# 2_MICROCONTROLADOR.net
KiCad netlist of a schematic drawn in Altium Designer
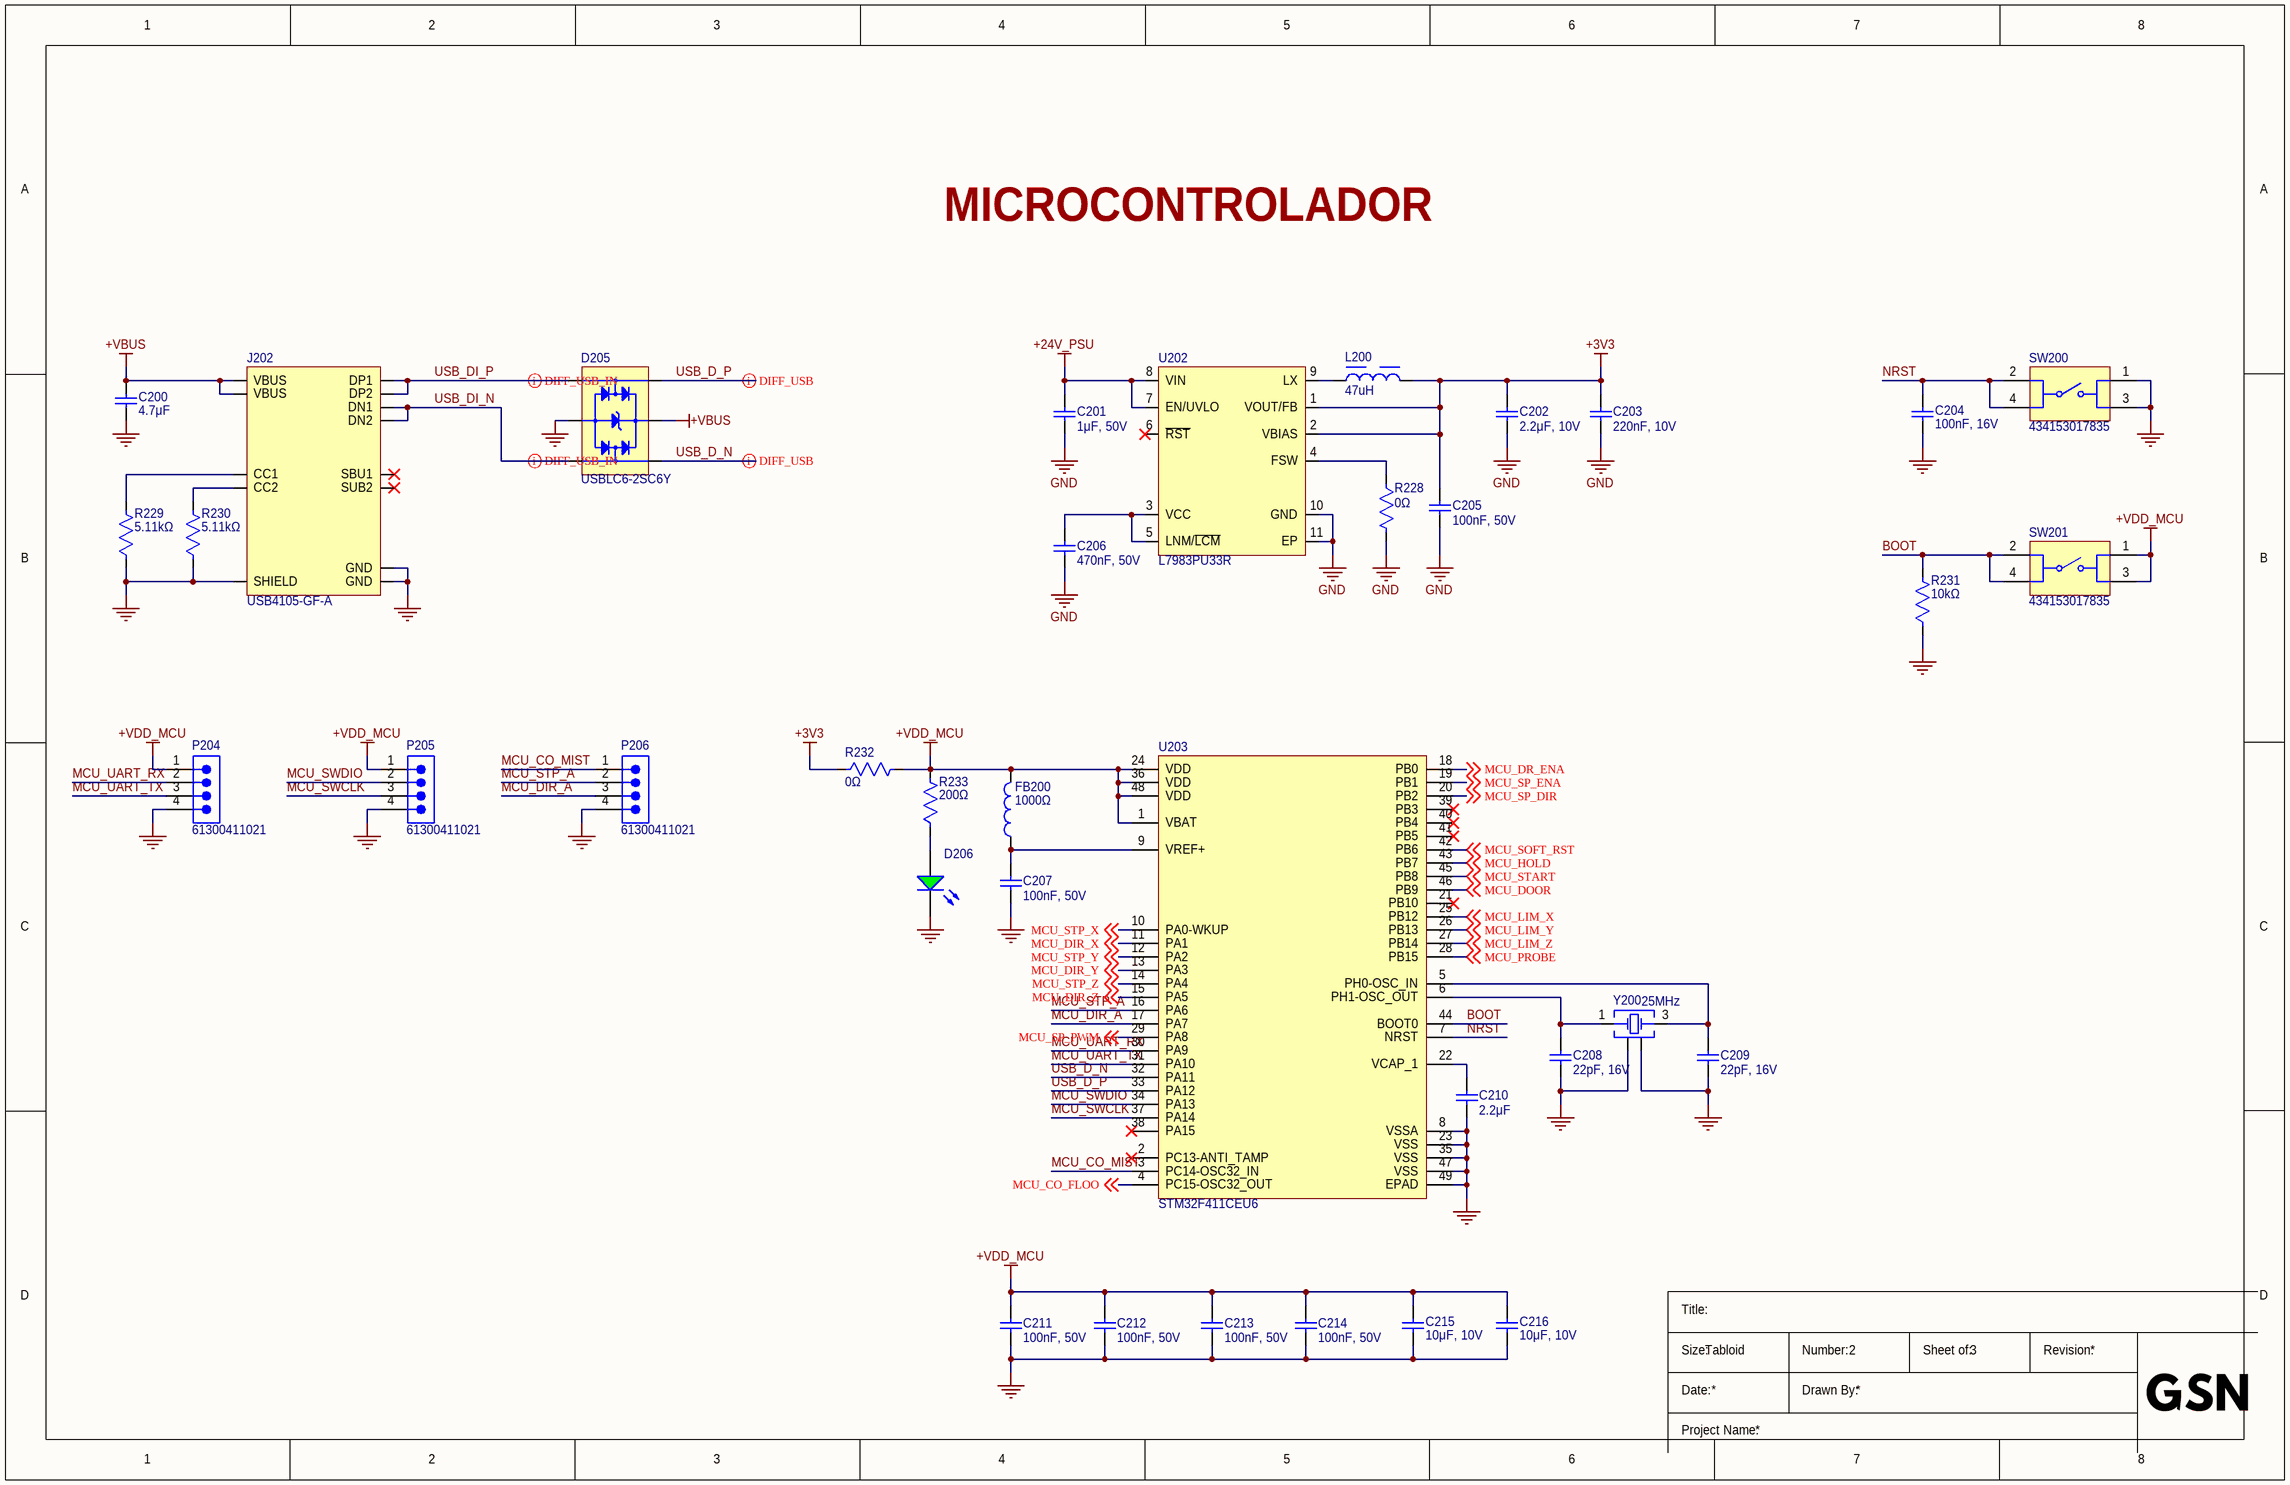
[diagram p0: 2_MICROCONTROLADOR.SchDoc]

(export (version "E")
  (design (tool "Eeschema 10.0.6"))
  (components
    (comp (ref "C200")
      (value "4.7μF")
      (footprint "WCAP-CSGP_0805_L2W1.25H1.25")
      (description "WCAP-CSGP Multilayer Ceramic Chip Capacitor, General Purpose, size 0805, 4.7μF, 16V")
      (fields
        (field (name "MANUFACTURER PART NUMBER") "885012207053")
        (field (name "MANUFACTURER") "Wurth Elektronik")
      )
      (libsource (lib "WE - Passive Components") (part "Capacitor_Non-Polarized"))
    )
    (comp (ref "C201")
      (value "1μF, 50V")
      (footprint "WCAP-CSGP_0805_L2W1.25H1.25")
      (description "WCAP-CSGP Multilayer Ceramic Chip Capacitor, General Purpose, size 0805, 1μF, 50V")
      (fields
        (field (name "MANUFACTURER PART NUMBER") "885012207103R")
        (field (name "MANUFACTURER") "Wurth Elektronik")
      )
      (libsource (lib "WE - Passive Components") (part "Capacitor_Non-Polarized"))
    )
    (comp (ref "C202")
      (value "2.2μF, 10V")
      (footprint "WCAP-CSGP_0603_L1.6W0.8H0.8_Wave")
      (description "WCAP-CSGP Multilayer Ceramic Chip Capacitor, General Purpose, size 0603, 2.2μF, 10V")
      (fields
        (field (name "MANUFACTURER PART NUMBER") "885012206027")
        (field (name "MANUFACTURER") "Wurth Elektronik")
      )
      (libsource (lib "WE - Passive Components") (part "Capacitor_Non-Polarized"))
    )
    (comp (ref "C203")
      (value "220nF, 10V")
      (footprint "WCAP-CSGP_0603_L1.6W0.8H0.8_Wave")
      (description "WCAP-CSGP Multilayer Ceramic Chip Capacitor, General Purpose, size 0603, 220nF, 10V")
      (fields
        (field (name "MANUFACTURER PART NUMBER") "885012206022")
        (field (name "MANUFACTURER") "Wurth Elektronik")
      )
      (libsource (lib "WE - Passive Components") (part "Capacitor_Non-Polarized"))
    )
    (comp (ref "C204")
      (value "100nF, 16V")
      (footprint "WCAP-CSGP_0603_L1.6W0.8H0.8_Wave")
      (description "WCAP-CSGP Multilayer Ceramic Chip Capacitor, General Purpose, size 0603, 100nF, 16V")
      (fields
        (field (name "MANUFACTURER PART NUMBER") "885012206046")
        (field (name "MANUFACTURER") "Wurth Elektronik")
      )
      (libsource (lib "WE - Passive Components") (part "Capacitor_Non-Polarized"))
    )
    (comp (ref "C205")
      (value "100nF, 50V")
      (footprint "WCAP-CSGP_0603_L1.6W0.8H0.8_Wave")
      (description "WCAP-CSGP Multilayer Ceramic Chip Capacitor, General Purpose, size 0603, 100nF, 50V")
      (fields
        (field (name "MANUFACTURER PART NUMBER") "885012206095")
        (field (name "MANUFACTURER") "Wurth Elektronik")
      )
      (libsource (lib "WE - Passive Components") (part "Capacitor_Non-Polarized"))
    )
    (comp (ref "C206")
      (value "470nF, 50V")
      (footprint "WCAP-CSGP_0805_L2W1.25H1.25")
      (description "WCAP-CSGP Multilayer Ceramic Chip Capacitor, General Purpose, size 0805, 470nF, 50V")
      (fields
        (field (name "MANUFACTURER PART NUMBER") "885012207102")
        (field (name "MANUFACTURER") "Wurth Elektronik")
      )
      (libsource (lib "WE - Passive Components") (part "Capacitor_Non-Polarized"))
    )
    (comp (ref "C207")
      (value "100nF, 50V")
      (footprint "WCAP-CSGP_0603_L1.6W0.8H0.8_Wave")
      (description "WCAP-CSGP Multilayer Ceramic Chip Capacitor, General Purpose, size 0603, 100nF, 50V")
      (fields
        (field (name "MANUFACTURER PART NUMBER") "885012206095")
        (field (name "MANUFACTURER") "Wurth Elektronik")
      )
      (libsource (lib "WE - Passive Components") (part "Capacitor_Non-Polarized"))
    )
    (comp (ref "C208")
      (value "22pF, 16V")
      (footprint "WCAP-CSGP_0603_L1.6W0.8H0.8_Wave")
      (description "WCAP-CSGP Multilayer Ceramic Chip Capacitor, General Purpose, size 0603, 22pF, 16V")
      (fields
        (field (name "MANUFACTURER PART NUMBER") "885012006019")
        (field (name "MANUFACTURER") "Wurth Elektronik")
      )
      (libsource (lib "WE - Passive Components") (part "Capacitor_Non-Polarized"))
    )
    (comp (ref "C209")
      (value "22pF, 16V")
      (footprint "WCAP-CSGP_0603_L1.6W0.8H0.8_Wave")
      (description "WCAP-CSGP Multilayer Ceramic Chip Capacitor, General Purpose, size 0603, 22pF, 16V")
      (fields
        (field (name "MANUFACTURER PART NUMBER") "885012006019")
        (field (name "MANUFACTURER") "Wurth Elektronik")
      )
      (libsource (lib "WE - Passive Components") (part "Capacitor_Non-Polarized"))
    )
    (comp (ref "C210")
      (value "2.2μF")
      (footprint "WCAP-CSGP_0603_L1.6W0.8H0.8_Wave")
      (description "WCAP-CSGP Multilayer Ceramic Chip Capacitor, General Purpose, size 0603, 2.2μF, 6.3V")
      (fields
        (field (name "MANUFACTURER PART NUMBER") "885012106004")
        (field (name "MANUFACTURER") "Wurth Elektronik")
      )
      (libsource (lib "WE - Passive Components") (part "Capacitor_Non-Polarized"))
    )
    (comp (ref "C211")
      (value "100nF, 50V")
      (footprint "WCAP-CSGP_0603_L1.6W0.8H0.8_Wave")
      (description "WCAP-CSGP Multilayer Ceramic Chip Capacitor, General Purpose, size 0603, 100nF, 50V")
      (fields
        (field (name "MANUFACTURER PART NUMBER") "885012206095")
        (field (name "MANUFACTURER") "Wurth Elektronik")
      )
      (libsource (lib "WE - Passive Components") (part "Capacitor_Non-Polarized"))
    )
    (comp (ref "C212")
      (value "100nF, 50V")
      (footprint "WCAP-CSGP_0603_L1.6W0.8H0.8_Wave")
      (description "WCAP-CSGP Multilayer Ceramic Chip Capacitor, General Purpose, size 0603, 100nF, 50V")
      (fields
        (field (name "MANUFACTURER PART NUMBER") "885012206095")
        (field (name "MANUFACTURER") "Wurth Elektronik")
      )
      (libsource (lib "WE - Passive Components") (part "Capacitor_Non-Polarized"))
    )
    (comp (ref "C213")
      (value "100nF, 50V")
      (footprint "WCAP-CSGP_0603_L1.6W0.8H0.8_Wave")
      (description "WCAP-CSGP Multilayer Ceramic Chip Capacitor, General Purpose, size 0603, 100nF, 50V")
      (fields
        (field (name "MANUFACTURER PART NUMBER") "885012206095")
        (field (name "MANUFACTURER") "Wurth Elektronik")
      )
      (libsource (lib "WE - Passive Components") (part "Capacitor_Non-Polarized"))
    )
    (comp (ref "C214")
      (value "100nF, 50V")
      (footprint "WCAP-CSGP_0603_L1.6W0.8H0.8_Wave")
      (description "WCAP-CSGP Multilayer Ceramic Chip Capacitor, General Purpose, size 0603, 100nF, 50V")
      (fields
        (field (name "MANUFACTURER PART NUMBER") "885012206095")
        (field (name "MANUFACTURER") "Wurth Elektronik")
      )
      (libsource (lib "WE - Passive Components") (part "Capacitor_Non-Polarized"))
    )
    (comp (ref "C215")
      (value "10μF, 10V")
      (footprint "WCAP-CSGP_0805_L2W1.25H1.25")
      (description "WCAP-CSGP Multilayer Ceramic Chip Capacitor, General Purpose, size 0805, 10μF, 10V")
      (fields
        (field (name "MANUFACTURER PART NUMBER") "885012207026")
        (field (name "MANUFACTURER") "Wurth Elektronik")
      )
      (libsource (lib "WE - Passive Components") (part "Capacitor_Non-Polarized"))
    )
    (comp (ref "C216")
      (value "10μF, 10V")
      (footprint "WCAP-CSGP_0805_L2W1.25H1.25")
      (description "WCAP-CSGP Multilayer Ceramic Chip Capacitor, General Purpose, size 0805, 10μF, 10V")
      (fields
        (field (name "MANUFACTURER PART NUMBER") "885012207026")
        (field (name "MANUFACTURER") "Wurth Elektronik")
      )
      (libsource (lib "WE - Passive Components") (part "Capacitor_Non-Polarized"))
    )
    (comp (ref "D205")
      (value "USBLC6-2SC6Y")
      (footprint "SOT-23-6")
      (description "TVS DIODE 5.25VWM 17VC SOT23-6")
      (fields (field (name "MANUFACTURER") "STMicroelectronics"))
      (libsource (lib "TVS-Diodes") (part "USBLC6-2SC6Y"))
    )
    (comp (ref "D206")
      (value "Bright Green, 2V, 140deg")
      (footprint "WL-SMCW_0603_150060xx75000")
      (description "WL-SMCW Mono-color Chip LED Waterclear, SMT, size 0603, Bright Green, 2V, 140°")
      (fields
        (field (name "MANUFACTURER PART NUMBER") "150060VS75000")
        (field (name "MANUFACTURER") "Wurth Elektronik")
      )
      (libsource (lib "WE - Optoelectronic Components") (part "LED_Green_2A-1K"))
    )
    (comp (ref "FB200")
      (value "1000Ω")
      (footprint "WE-CBF_0603_L1.6W0.8H0.8_HS_WB")
      (description "WE-CBF SMT EMI Suppression Ferrite Bead, size 0603, 1000Ω, 0.65A")
      (fields
        (field (name "MANUFACTURER PART NUMBER") "74279266")
        (field (name "MANUFACTURER") "Wurth Elektronik")
      )
      (libsource (lib "WE - Passive Components") (part "Ferrite"))
    )
    (comp (ref "J202")
      (value "USB4105-GF-A")
      (footprint "USB4105-GF-A")
      (description "CONN RCP USB2.0 TYP C 16P SMD RA")
      (fields (field (name "MANUFACTURER") "Global Connector Technology"))
      (libsource (lib "Connectors") (part "USB4105-GF-A"))
    )
    (comp (ref "L200")
      (value "47uH")
      (footprint "WE-MAIA_3015")
      (description "WE-MAIA SMT Power Inductor, size 3015, 47uH, 0.5A, 2300mohm")
      (fields
        (field (name "MANUFACTURER PART NUMBER") "78438335470")
        (field (name "MANUFACTURER") "Wurth Elektronik")
      )
      (libsource (lib "WE - Passive Components") (part "Inductor - 3"))
    )
    (comp (ref "P204")
      (value "61300411021")
      (footprint "61300411021")
      (description "WR-PHD Pin Header, THT, Angled, pitch 2.54mm, 1 Row, 4P")
      (fields (field (name "MANUFACTURER") "Wurth Elektronik"))
      (libsource (lib "WE - Electromechanical Components") (part "Header_Male_1R_04P"))
    )
    (comp (ref "P205")
      (value "61300411021")
      (footprint "61300411021")
      (description "WR-PHD Pin Header, THT, Angled, pitch 2.54mm, 1 Row, 4P")
      (fields (field (name "MANUFACTURER") "Wurth Elektronik"))
      (libsource (lib "WE - Electromechanical Components") (part "Header_Male_1R_04P"))
    )
    (comp (ref "P206")
      (value "61300411021")
      (footprint "61300411021")
      (description "WR-PHD Pin Header, THT, Angled, pitch 2.54mm, 1 Row, 4P")
      (fields (field (name "MANUFACTURER") "Wurth Elektronik"))
      (libsource (lib "WE - Electromechanical Components") (part "Header_Male_1R_04P"))
    )
    (comp (ref "R228")
      (value "0Ω")
      (footprint "0603-WAVE")
      (description "RES 0 OHM 1% 1/10W 0603")
      (fields
        (field (name "MANUFACTURER PART NUMBER") "RC0603FR-070RL")
        (field (name "MANUFACTURER") "Yageo Group")
      )
      (libsource (lib "Resistors-0603-E96-Yageo") (part "RC0603FR-070RL"))
    )
    (comp (ref "R229")
      (value "5.11kΩ")
      (footprint "0603-WAVE")
      (description "RES 5.11K OHM 1% 1/10W 0603")
      (fields
        (field (name "MANUFACTURER PART NUMBER") "RC0603FR-075K11L")
        (field (name "MANUFACTURER") "Yageo Group")
      )
      (libsource (lib "Resistors-0603-E96-Yageo") (part "RC0603FR-075K11L"))
    )
    (comp (ref "R230")
      (value "5.11kΩ")
      (footprint "0603-WAVE")
      (description "RES 5.11K OHM 1% 1/10W 0603")
      (fields
        (field (name "MANUFACTURER PART NUMBER") "RC0603FR-075K11L")
        (field (name "MANUFACTURER") "Yageo Group")
      )
      (libsource (lib "Resistors-0603-E96-Yageo") (part "RC0603FR-075K11L"))
    )
    (comp (ref "R231")
      (value "10kΩ")
      (footprint "0603-WAVE")
      (description "RES 10K OHM 1% 1/10W 0603")
      (fields
        (field (name "MANUFACTURER PART NUMBER") "RC0603FR-0710KL")
        (field (name "MANUFACTURER") "Yageo Group")
      )
      (libsource (lib "Resistors-0603-E96-Yageo") (part "RC0603FR-0710KL"))
    )
    (comp (ref "R232")
      (value "0Ω")
      (footprint "0805-WAVE")
      (description "RES 0 OHM 1% 1/8W 0805")
      (fields
        (field (name "MANUFACTURER") "Yageo Group")
        (field (name "MANUFACTURER PART NUMBER") "RC0805FR-070RL")
      )
      (libsource (lib "Resistors-0805-E96-Yageo") (part "RC0805FR-070RL"))
    )
    (comp (ref "R233")
      (value "200Ω")
      (footprint "0603-WAVE")
      (description "RES 200 OHM 1% 1/10W 0603")
      (fields
        (field (name "MANUFACTURER PART NUMBER") "RC0603FR-07200RL")
        (field (name "MANUFACTURER") "Yageo Group")
      )
      (libsource (lib "Resistors-0603-E96-Yageo") (part "RC0603FR-07200RL"))
    )
    (comp (ref "SW200")
      (value "434153017835")
      (footprint "434153017835")
      (description "WS-TASV J-Bend SMT Tact Switch, 3.5mm x 2.9mm x 1.7mm, SPST-NO, 350gf, 12V, 50mA")
      (fields (field (name "MANUFACTURER") "Wurth Elektronik"))
      (libsource (lib "WE - Electromechanical Components") (part "SPST-NO_4P_24-13"))
    )
    (comp (ref "SW201")
      (value "434153017835")
      (footprint "434153017835")
      (description "WS-TASV J-Bend SMT Tact Switch, 3.5mm x 2.9mm x 1.7mm, SPST-NO, 350gf, 12V, 50mA")
      (fields (field (name "MANUFACTURER") "Wurth Elektronik"))
      (libsource (lib "WE - Electromechanical Components") (part "SPST-NO_4P_24-13"))
    )
    (comp (ref "U202")
      (value "L7983PU33R")
      (footprint "10-WFDFN-EP")
      (description "IC REG BUCK 3.3V 300MA 10DFN")
      (fields (field (name "MANUFACTURER") "STMicroelectronics"))
      (libsource (lib "Voltage-Regulators") (part "L7983PU33R"))
    )
    (comp (ref "U203")
      (value "STM32F411CEU6")
      (footprint "UFQFN-48-7X7_EXPOSED_PAD")
      (description "IC MCU 32BIT 512KB FLSH 48UFQFPN")
      (fields (field (name "MANUFACTURER") "STMicroelectronics"))
      (libsource (lib "Microcontrollers") (part "STM32F411CEU6"))
    )
    (comp (ref "Y200")
      (value "25MHz")
      (footprint "WE-XTAL_CFPX-180")
      (description "WE-XTAL Quartz Crystal, CFPX-180, 25MHz, +/-50ppm")
      (fields
        (field (name "MANUFACTURER PART NUMBER") "830055474")
        (field (name "MANUFACTURER") "Wurth Elektronik")
      )
      (libsource (lib "WE - Passive Components") (part "WE-XTAL_CFPX-180"))
    )
  )
  (nets
    (net (code "1") (name "+3V3") (class "Default")
      (node (ref "C202") (pin "2") (pinfunction "2_2") (pintype "passive"))
      (node (ref "C203") (pin "2") (pinfunction "2_2") (pintype "passive"))
      (node (ref "C205") (pin "2") (pinfunction "2_2") (pintype "passive"))
      (node (ref "L200") (pin "2") (pinfunction "2_2") (pintype "passive"))
      (node (ref "R232") (pin "1") (pinfunction "1_1") (pintype "passive"))
      (node (ref "U202") (pin "1") (pinfunction "VOUT/FB_1") (pintype "passive"))
      (node (ref "U202") (pin "2") (pinfunction "VBIAS_2") (pintype "passive"))
    )
    (net (code "2") (name "+24V_PSU") (class "Default")
      (node (ref "C201") (pin "2") (pinfunction "2_2") (pintype "passive"))
      (node (ref "U202") (pin "7") (pinfunction "EN/UVLO_7") (pintype "passive"))
      (node (ref "U202") (pin "8") (pinfunction "VIN_8") (pintype "passive"))
    )
    (net (code "3") (name "+VBUS") (class "Default")
      (node (ref "C200") (pin "2") (pinfunction "2_2") (pintype "passive"))
      (node (ref "D205") (pin "5") (pinfunction "VBUS_5") (pintype "passive"))
      (node (ref "J202") (pin "A4_B9") (pinfunction "VBUS_A4_B9") (pintype "passive"))
      (node (ref "J202") (pin "B4_A9") (pinfunction "VBUS_B4_A9") (pintype "passive"))
    )
    (net (code "4") (name "+VDD_MCU") (class "Default")
      (node (ref "C211") (pin "2") (pinfunction "2_2") (pintype "passive"))
      (node (ref "C212") (pin "2") (pinfunction "2_2") (pintype "passive"))
      (node (ref "C213") (pin "2") (pinfunction "2_2") (pintype "passive"))
      (node (ref "C214") (pin "2") (pinfunction "2_2") (pintype "passive"))
      (node (ref "C215") (pin "2") (pinfunction "2_2") (pintype "passive"))
      (node (ref "C216") (pin "2") (pinfunction "2_2") (pintype "passive"))
      (node (ref "FB200") (pin "2") (pinfunction "2_2") (pintype "passive"))
      (node (ref "P204") (pin "1") (pinfunction "1_1") (pintype "passive"))
      (node (ref "P205") (pin "1") (pinfunction "1_1") (pintype "passive"))
      (node (ref "R232") (pin "2") (pinfunction "2_2") (pintype "passive"))
      (node (ref "R233") (pin "2") (pinfunction "2_2") (pintype "passive"))
      (node (ref "SW201") (pin "1") (pinfunction "1_1") (pintype "passive"))
      (node (ref "SW201") (pin "3") (pinfunction "3_3") (pintype "passive"))
      (node (ref "U203") (pin "1") (pinfunction "VBAT_1") (pintype "passive"))
      (node (ref "U203") (pin "24") (pinfunction "VDD_24") (pintype "passive"))
      (node (ref "U203") (pin "36") (pinfunction "VDD_36") (pintype "passive"))
      (node (ref "U203") (pin "48") (pinfunction "VDD_48") (pintype "passive"))
    )
    (net (code "5") (name "/BOOT") (class "Default")
      (node (ref "R231") (pin "2") (pinfunction "2_2") (pintype "passive"))
      (node (ref "SW201") (pin "2") (pinfunction "2_2") (pintype "passive"))
      (node (ref "SW201") (pin "4") (pinfunction "4_4") (pintype "passive"))
      (node (ref "U203") (pin "44") (pinfunction "BOOT0_44") (pintype "passive"))
    )
    (net (code "6") (name "/MCU_CO_MIST") (class "Default")
      (node (ref "P206") (pin "1") (pinfunction "1_1") (pintype "passive"))
      (node (ref "U203") (pin "3") (pinfunction "PC14-OSC32_IN_3") (pintype "passive"))
    )
    (net (code "7") (name "/MCU_DIR_A") (class "Default")
      (node (ref "P206") (pin "3") (pinfunction "3_3") (pintype "passive"))
      (node (ref "U203") (pin "17") (pinfunction "PA7_17") (pintype "passive"))
    )
    (net (code "8") (name "/MCU_STP_A") (class "Default")
      (node (ref "P206") (pin "2") (pinfunction "2_2") (pintype "passive"))
      (node (ref "U203") (pin "16") (pinfunction "PA6_16") (pintype "passive"))
    )
    (net (code "9") (name "/MCU_SWCLK") (class "Default")
      (node (ref "P205") (pin "3") (pinfunction "3_3") (pintype "passive"))
      (node (ref "U203") (pin "37") (pinfunction "PA14_37") (pintype "passive"))
    )
    (net (code "10") (name "/MCU_SWDIO") (class "Default")
      (node (ref "P205") (pin "2") (pinfunction "2_2") (pintype "passive"))
      (node (ref "U203") (pin "34") (pinfunction "PA13_34") (pintype "passive"))
    )
    (net (code "11") (name "/MCU_UART_RX") (class "Default")
      (node (ref "P204") (pin "2") (pinfunction "2_2") (pintype "passive"))
      (node (ref "U203") (pin "30") (pinfunction "PA9_30") (pintype "passive"))
    )
    (net (code "12") (name "/MCU_UART_TX") (class "Default")
      (node (ref "P204") (pin "3") (pinfunction "3_3") (pintype "passive"))
      (node (ref "U203") (pin "31") (pinfunction "PA10_31") (pintype "passive"))
    )
    (net (code "13") (name "/NRST") (class "Default")
      (node (ref "C204") (pin "2") (pinfunction "2_2") (pintype "passive"))
      (node (ref "SW200") (pin "2") (pinfunction "2_2") (pintype "passive"))
      (node (ref "SW200") (pin "4") (pinfunction "4_4") (pintype "passive"))
      (node (ref "U203") (pin "7") (pinfunction "NRST_7") (pintype "passive"))
    )
    (net (code "14") (name "/USB_DI_N") (class "Default")
      (node (ref "D205") (pin "3") (pinfunction "IO2_3") (pintype "passive"))
      (node (ref "J202") (pin "A7") (pinfunction "DN1_A7") (pintype "passive"))
      (node (ref "J202") (pin "B7") (pinfunction "DN2_B7") (pintype "passive"))
    )
    (net (code "15") (name "/USB_DI_P") (class "Default")
      (node (ref "D205") (pin "1") (pinfunction "IO1_1") (pintype "passive"))
      (node (ref "J202") (pin "A6") (pinfunction "DP1_A6") (pintype "passive"))
      (node (ref "J202") (pin "B6") (pinfunction "DP2_B6") (pintype "passive"))
    )
    (net (code "16") (name "/USB_D_N") (class "Default")
      (node (ref "D205") (pin "4") (pinfunction "IO2_4") (pintype "passive"))
      (node (ref "U203") (pin "32") (pinfunction "PA11_32") (pintype "passive"))
    )
    (net (code "17") (name "/USB_D_P") (class "Default")
      (node (ref "D205") (pin "6") (pinfunction "IO1_6") (pintype "passive"))
      (node (ref "U203") (pin "33") (pinfunction "PA12_33") (pintype "passive"))
    )
    (net (code "18") (name "GND") (class "Default")
      (node (ref "C200") (pin "1") (pinfunction "1_1") (pintype "passive"))
      (node (ref "C201") (pin "1") (pinfunction "1_1") (pintype "passive"))
      (node (ref "C202") (pin "1") (pinfunction "1_1") (pintype "passive"))
      (node (ref "C203") (pin "1") (pinfunction "1_1") (pintype "passive"))
      (node (ref "C204") (pin "1") (pinfunction "1_1") (pintype "passive"))
      (node (ref "C205") (pin "1") (pinfunction "1_1") (pintype "passive"))
      (node (ref "C206") (pin "1") (pinfunction "1_1") (pintype "passive"))
      (node (ref "C207") (pin "1") (pinfunction "1_1") (pintype "passive"))
      (node (ref "C208") (pin "1") (pinfunction "1_1") (pintype "passive"))
      (node (ref "C209") (pin "1") (pinfunction "1_1") (pintype "passive"))
      (node (ref "C210") (pin "1") (pinfunction "1_1") (pintype "passive"))
      (node (ref "C211") (pin "1") (pinfunction "1_1") (pintype "passive"))
      (node (ref "C212") (pin "1") (pinfunction "1_1") (pintype "passive"))
      (node (ref "C213") (pin "1") (pinfunction "1_1") (pintype "passive"))
      (node (ref "C214") (pin "1") (pinfunction "1_1") (pintype "passive"))
      (node (ref "C215") (pin "1") (pinfunction "1_1") (pintype "passive"))
      (node (ref "C216") (pin "1") (pinfunction "1_1") (pintype "passive"))
      (node (ref "D205") (pin "2") (pinfunction "GND_2") (pintype "passive"))
      (node (ref "D206") (pin "1") (pinfunction "K_1") (pintype "passive"))
      (node (ref "J202") (pin "A1_B12") (pinfunction "GND_A1_B12") (pintype "power_in"))
      (node (ref "J202") (pin "B1_A12") (pinfunction "GND_B1_A12") (pintype "power_in"))
      (node (ref "J202") (pin "SH") (pinfunction "SHIELD_SH") (pintype "passive"))
      (node (ref "P204") (pin "4") (pinfunction "4_4") (pintype "passive"))
      (node (ref "P205") (pin "4") (pinfunction "4_4") (pintype "passive"))
      (node (ref "P206") (pin "4") (pinfunction "4_4") (pintype "passive"))
      (node (ref "R228") (pin "2") (pinfunction "2_2") (pintype "passive"))
      (node (ref "R229") (pin "1") (pinfunction "1_1") (pintype "passive"))
      (node (ref "R230") (pin "1") (pinfunction "1_1") (pintype "passive"))
      (node (ref "R231") (pin "1") (pinfunction "1_1") (pintype "passive"))
      (node (ref "SW200") (pin "1") (pinfunction "1_1") (pintype "passive"))
      (node (ref "SW200") (pin "3") (pinfunction "3_3") (pintype "passive"))
      (node (ref "U202") (pin "10") (pinfunction "GND_10") (pintype "passive"))
      (node (ref "U202") (pin "11") (pinfunction "EP_11") (pintype "passive"))
      (node (ref "U203") (pin "23") (pinfunction "VSS_23") (pintype "passive"))
      (node (ref "U203") (pin "35") (pinfunction "VSS_35") (pintype "passive"))
      (node (ref "U203") (pin "47") (pinfunction "VSS_47") (pintype "passive"))
      (node (ref "U203") (pin "49") (pinfunction "EPAD_49") (pintype "passive"))
      (node (ref "U203") (pin "8") (pinfunction "VSSA_8") (pintype "passive"))
      (node (ref "Y200") (pin "2") (pinfunction "GND&Lid_2") (pintype "passive"))
      (node (ref "Y200") (pin "4") (pinfunction "GND&Lid_4") (pintype "passive"))
    )
    (net (code "19") (name "MCU_CO_FLOO") (class "Default")
      (node (ref "U203") (pin "4") (pinfunction "PC15-OSC32_OUT_4") (pintype "passive"))
    )
    (net (code "20") (name "MCU_DIR_X") (class "Default")
      (node (ref "U203") (pin "11") (pinfunction "PA1_11") (pintype "passive"))
    )
    (net (code "21") (name "MCU_DIR_Y") (class "Default")
      (node (ref "U203") (pin "13") (pinfunction "PA3_13") (pintype "passive"))
    )
    (net (code "22") (name "MCU_DIR_Z") (class "Default")
      (node (ref "U203") (pin "15") (pinfunction "PA5_15") (pintype "passive"))
    )
    (net (code "23") (name "MCU_DOOR") (class "Default")
      (node (ref "U203") (pin "46") (pinfunction "PB9_46") (pintype "passive"))
    )
    (net (code "24") (name "MCU_DR_ENA") (class "Default")
      (node (ref "U203") (pin "18") (pinfunction "PB0_18") (pintype "passive"))
    )
    (net (code "25") (name "MCU_HOLD") (class "Default")
      (node (ref "U203") (pin "43") (pinfunction "PB7_43") (pintype "passive"))
    )
    (net (code "26") (name "MCU_LIM_X") (class "Default")
      (node (ref "U203") (pin "25") (pinfunction "PB12_25") (pintype "passive"))
    )
    (net (code "27") (name "MCU_LIM_Y") (class "Default")
      (node (ref "U203") (pin "26") (pinfunction "PB13_26") (pintype "passive"))
    )
    (net (code "28") (name "MCU_LIM_Z") (class "Default")
      (node (ref "U203") (pin "27") (pinfunction "PB14_27") (pintype "passive"))
    )
    (net (code "29") (name "MCU_PROBE") (class "Default")
      (node (ref "U203") (pin "28") (pinfunction "PB15_28") (pintype "passive"))
    )
    (net (code "30") (name "MCU_SOFT_RST") (class "Default")
      (node (ref "U203") (pin "42") (pinfunction "PB6_42") (pintype "passive"))
    )
    (net (code "31") (name "MCU_SP_DIR") (class "Default")
      (node (ref "U203") (pin "20") (pinfunction "PB2_20") (pintype "passive"))
    )
    (net (code "32") (name "MCU_SP_ENA") (class "Default")
      (node (ref "U203") (pin "19") (pinfunction "PB1_19") (pintype "passive"))
    )
    (net (code "33") (name "MCU_SP_PWM") (class "Default")
      (node (ref "U203") (pin "29") (pinfunction "PA8_29") (pintype "passive"))
    )
    (net (code "34") (name "MCU_START") (class "Default")
      (node (ref "U203") (pin "45") (pinfunction "PB8_45") (pintype "passive"))
    )
    (net (code "35") (name "MCU_STP_X") (class "Default")
      (node (ref "U203") (pin "10") (pinfunction "PA0-WKUP_10") (pintype "passive"))
    )
    (net (code "36") (name "MCU_STP_Y") (class "Default")
      (node (ref "U203") (pin "12") (pinfunction "PA2_12") (pintype "passive"))
    )
    (net (code "37") (name "MCU_STP_Z") (class "Default")
      (node (ref "U203") (pin "14") (pinfunction "PA4_14") (pintype "passive"))
    )
    (net (code "38") (name "Net-(D206-A)") (class "Default")
      (node (ref "D206") (pin "2") (pinfunction "A_2") (pintype "passive"))
      (node (ref "R233") (pin "1") (pinfunction "1_1") (pintype "passive"))
    )
    (net (code "39") (name "Net-(J202-CC1)") (class "Default")
      (node (ref "J202") (pin "A5") (pinfunction "CC1_A5") (pintype "passive"))
      (node (ref "R229") (pin "2") (pinfunction "2_2") (pintype "passive"))
    )
    (net (code "40") (name "Net-(J202-CC2)") (class "Default")
      (node (ref "J202") (pin "B5") (pinfunction "CC2_B5") (pintype "passive"))
      (node (ref "R230") (pin "2") (pinfunction "2_2") (pintype "passive"))
    )
    (net (code "41") (name "Net-(U202-FSW)") (class "Default")
      (node (ref "R228") (pin "1") (pinfunction "1_1") (pintype "passive"))
      (node (ref "U202") (pin "4") (pinfunction "FSW_4") (pintype "passive"))
    )
    (net (code "42") (name "Net-(U202-LNM{slash}~{LCM})") (class "Default")
      (node (ref "C206") (pin "2") (pinfunction "2_2") (pintype "passive"))
      (node (ref "U202") (pin "3") (pinfunction "VCC_3") (pintype "passive"))
      (node (ref "U202") (pin "5") (pinfunction "LNM/~{LCM}_5") (pintype "passive"))
    )
    (net (code "43") (name "Net-(U202-LX)") (class "Default")
      (node (ref "L200") (pin "1") (pinfunction "1_1") (pintype "passive"))
      (node (ref "U202") (pin "9") (pinfunction "LX_9") (pintype "passive"))
    )
    (net (code "44") (name "Net-(U203-PH0-OSC_IN)") (class "Default")
      (node (ref "C209") (pin "2") (pinfunction "2_2") (pintype "passive"))
      (node (ref "U203") (pin "5") (pinfunction "PH0-OSC_IN_5") (pintype "passive"))
      (node (ref "Y200") (pin "3") (pinfunction "Crystal_3") (pintype "passive"))
    )
    (net (code "45") (name "Net-(U203-PH1-OSC_OUT)") (class "Default")
      (node (ref "C208") (pin "2") (pinfunction "2_2") (pintype "passive"))
      (node (ref "U203") (pin "6") (pinfunction "PH1-OSC_OUT_6") (pintype "passive"))
      (node (ref "Y200") (pin "1") (pinfunction "Crystal_1") (pintype "passive"))
    )
    (net (code "46") (name "Net-(U203-VCAP_1)") (class "Default")
      (node (ref "C210") (pin "2") (pinfunction "2_2") (pintype "passive"))
      (node (ref "U203") (pin "22") (pinfunction "VCAP_1_22") (pintype "passive"))
    )
    (net (code "47") (name "Net-(U203-VREF+)") (class "Default")
      (node (ref "C207") (pin "2") (pinfunction "2_2") (pintype "passive"))
      (node (ref "FB200") (pin "1") (pinfunction "1_1") (pintype "passive"))
      (node (ref "U203") (pin "9") (pinfunction "VREF+_9") (pintype "passive"))
    )
    (net (code "48") (name "unconnected-(J202-SBU1-PadA8)") (class "Default")
      (node (ref "J202") (pin "A8") (pinfunction "SBU1_A8") (pintype "passive+no_connect"))
    )
    (net (code "49") (name "unconnected-(J202-SUB2-PadB8)") (class "Default")
      (node (ref "J202") (pin "B8") (pinfunction "SUB2_B8") (pintype "passive+no_connect"))
    )
    (net (code "50") (name "unconnected-(U202-~{RST}-Pad6)") (class "Default")
      (node (ref "U202") (pin "6") (pinfunction "~{RST}_6") (pintype "passive+no_connect"))
    )
    (net (code "51") (name "unconnected-(U203-PA15-Pad38)") (class "Default")
      (node (ref "U203") (pin "38") (pinfunction "PA15_38") (pintype "passive+no_connect"))
    )
    (net (code "52") (name "unconnected-(U203-PB3-Pad39)") (class "Default")
      (node (ref "U203") (pin "39") (pinfunction "PB3_39") (pintype "passive+no_connect"))
    )
    (net (code "53") (name "unconnected-(U203-PB4-Pad40)") (class "Default")
      (node (ref "U203") (pin "40") (pinfunction "PB4_40") (pintype "passive+no_connect"))
    )
    (net (code "54") (name "unconnected-(U203-PB5-Pad41)") (class "Default")
      (node (ref "U203") (pin "41") (pinfunction "PB5_41") (pintype "passive+no_connect"))
    )
    (net (code "55") (name "unconnected-(U203-PB10-Pad21)") (class "Default")
      (node (ref "U203") (pin "21") (pinfunction "PB10_21") (pintype "passive+no_connect"))
    )
    (net (code "56") (name "unconnected-(U203-PC13-ANTI_TAMP-Pad2)") (class "Default")
      (node (ref "U203") (pin "2") (pinfunction "PC13-ANTI_TAMP_2") (pintype "passive+no_connect"))
    )
  )
)
